# Interface.net
KiCad netlist of a schematic drawn in Altium Designer
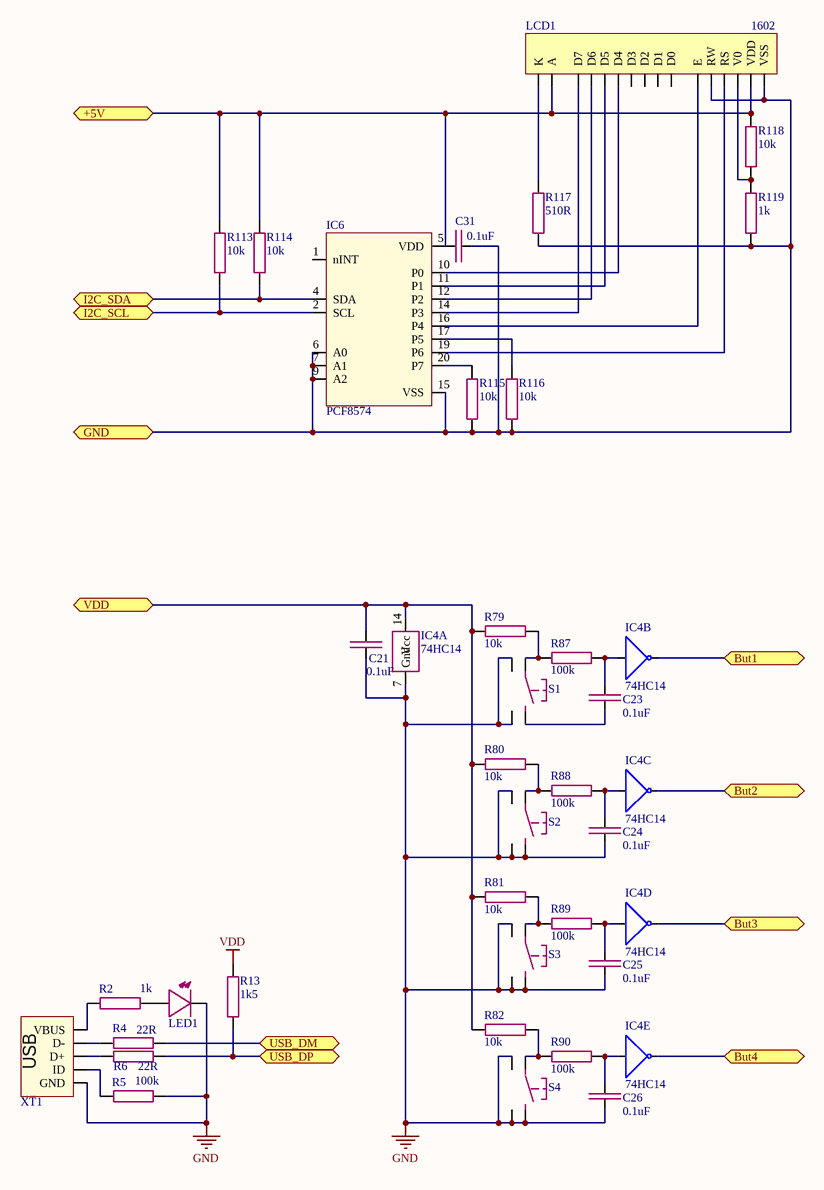
[diagram p0: Interface.SchDoc]

(export (version "E")
  (design (tool "Eeschema 10.0.6"))
  (components
    (comp (ref "C21")
      (value "0.1uF")
      (footprint "PcbLib:C0603")
      (description "CAP CER 0.1UF 50V X7R 0603")
      (fields (field (name "MANUFACTURER PART NUMBER") "GMK316F475ZG-T"))
      (libsource (lib "RCU") (part "GMK316F475ZG-T"))
    )
    (comp (ref "C23")
      (value "0.1uF")
      (footprint "PcbLib:C0603")
      (description "CAP CER 0.1UF 50V X7R 0603")
      (fields (field (name "MANUFACTURER PART NUMBER") "GMK316F475ZG-T"))
      (libsource (lib "RCU") (part "GMK316F475ZG-T"))
    )
    (comp (ref "C24")
      (value "0.1uF")
      (footprint "PcbLib:C0603")
      (description "CAP CER 0.1UF 50V X7R 0603")
      (fields (field (name "MANUFACTURER PART NUMBER") "GMK316F475ZG-T"))
      (libsource (lib "RCU") (part "GMK316F475ZG-T"))
    )
    (comp (ref "C25")
      (value "0.1uF")
      (footprint "PcbLib:C0603")
      (description "CAP CER 0.1UF 50V X7R 0603")
      (fields (field (name "MANUFACTURER PART NUMBER") "GMK316F475ZG-T"))
      (libsource (lib "RCU") (part "GMK316F475ZG-T"))
    )
    (comp (ref "C26")
      (value "0.1uF")
      (footprint "PcbLib:C0603")
      (description "CAP CER 0.1UF 50V X7R 0603")
      (fields (field (name "MANUFACTURER PART NUMBER") "GMK316F475ZG-T"))
      (libsource (lib "RCU") (part "GMK316F475ZG-T"))
    )
    (comp (ref "C31")
      (value "0.1uF")
      (footprint "PcbLib:C0603")
      (description "CAP CER 0.1UF 50V X7R 0603")
      (fields (field (name "MANUFACTURER PART NUMBER") "GMK316F475ZG-T"))
      (libsource (lib "RCU") (part "GMK316F475ZG-T"))
    )
    (comp (ref "IC4")
      (value "74HC14")
      (footprint "PcbLib:SSOP14")
      (description "IC INVERTER HEX SCHMITT 14SOIC")
      (fields (field (name "MANUFACTURER PART NUMBER") "MC74HC14ADR2G"))
      (libsource (lib "RCU") (part "MC74HC14ADR2G"))
    )
    (comp (ref "IC6")
      (value "PCF8574")
      (footprint "PcbLib:SSOP-20N")
      (description "IC I/O EXPANDER I2C 8B 20TSSOP")
      (fields (field (name "MANUFACTURER PART NUMBER") "PCF8574APWR"))
      (libsource (lib "RCU") (part "PCF8574APWR"))
    )
    (comp (ref "LCD1")
      (value "1602")
      (footprint "PcbLib:Display1602")
      (description "DISP 1602 THT")
      (libsource (lib "RCU") (part "Display1602"))
    )
    (comp (ref "LED1")
      (value "Green LED")
      (footprint "PcbLib:LED0805")
      (description "LED GREEN DIFFUSED 0805 SMD")
      (fields (field (name "MANUFACTURER PART NUMBER") "LG R971-KN-1"))
      (libsource (lib "RCU") (part "LG R971-KN-1"))
    )
    (comp (ref "R2")
      (value "1k")
      (footprint "PcbLib:R0603")
      (description "RES SMD 1K OHM 5% 1/10W 0603")
      (fields (field (name "MANUFACTURER PART NUMBER") "ERJ-3GEYJ102V"))
      (libsource (lib "RCU") (part "ERJ-3GEYJ102V"))
    )
    (comp (ref "R4")
      (value "22R")
      (footprint "PcbLib:R0603")
      (description "RES SMD 22 OHM 1% 1/10W 0603")
      (fields (field (name "MANUFACTURER PART NUMBER") "CRCW060322R0FKEA"))
      (libsource (lib "RCU") (part "CRCW060322R0FKEA"))
    )
    (comp (ref "R5")
      (value "100k")
      (footprint "PcbLib:R0603")
      (description "RES SMD 100K OHM 5% 1/10W 0603")
      (fields (field (name "MANUFACTURER PART NUMBER") "ERJ-S03J104V"))
      (libsource (lib "RCU") (part "ERJ-S03J104V"))
    )
    (comp (ref "R6")
      (value "22R")
      (footprint "PcbLib:R0603")
      (description "RES SMD 22 OHM 1% 1/10W 0603")
      (fields (field (name "MANUFACTURER PART NUMBER") "CRCW060322R0FKEA"))
      (libsource (lib "RCU") (part "CRCW060322R0FKEA"))
    )
    (comp (ref "R13")
      (value "1k5")
      (footprint "PcbLib:R0603")
      (description "RES SMD 1K5 OHM 5% 1/10W 0603")
      (fields (field (name "MANUFACTURER PART NUMBER") "CRCW06031K50JNTABC"))
      (libsource (lib "RCU") (part "CRCW06031K50JNTABC"))
    )
    (comp (ref "R79")
      (value "10k")
      (footprint "PcbLib:R0603")
      (description "RES SMD 10K OHM 5% 1/10W 0603")
      (fields (field (name "MANUFACTURER PART NUMBER") "ERJ-S03J103V"))
      (libsource (lib "RCU") (part "ERJ-S03J103V"))
    )
    (comp (ref "R80")
      (value "10k")
      (footprint "PcbLib:R0603")
      (description "RES SMD 10K OHM 5% 1/10W 0603")
      (fields (field (name "MANUFACTURER PART NUMBER") "ERJ-S03J103V"))
      (libsource (lib "RCU") (part "ERJ-S03J103V"))
    )
    (comp (ref "R81")
      (value "10k")
      (footprint "PcbLib:R0603")
      (description "RES SMD 10K OHM 5% 1/10W 0603")
      (fields (field (name "MANUFACTURER PART NUMBER") "ERJ-S03J103V"))
      (libsource (lib "RCU") (part "ERJ-S03J103V"))
    )
    (comp (ref "R82")
      (value "10k")
      (footprint "PcbLib:R0603")
      (description "RES SMD 10K OHM 5% 1/10W 0603")
      (fields (field (name "MANUFACTURER PART NUMBER") "ERJ-S03J103V"))
      (libsource (lib "RCU") (part "ERJ-S03J103V"))
    )
    (comp (ref "R87")
      (value "100k")
      (footprint "PcbLib:R0603")
      (description "RES SMD 100K OHM 5% 1/10W 0603")
      (fields (field (name "MANUFACTURER PART NUMBER") "ERJ-S03J104V"))
      (libsource (lib "RCU") (part "ERJ-S03J104V"))
    )
    (comp (ref "R88")
      (value "100k")
      (footprint "PcbLib:R0603")
      (description "RES SMD 100K OHM 5% 1/10W 0603")
      (fields (field (name "MANUFACTURER PART NUMBER") "ERJ-S03J104V"))
      (libsource (lib "RCU") (part "ERJ-S03J104V"))
    )
    (comp (ref "R89")
      (value "100k")
      (footprint "PcbLib:R0603")
      (description "RES SMD 100K OHM 5% 1/10W 0603")
      (fields (field (name "MANUFACTURER PART NUMBER") "ERJ-S03J104V"))
      (libsource (lib "RCU") (part "ERJ-S03J104V"))
    )
    (comp (ref "R90")
      (value "100k")
      (footprint "PcbLib:R0603")
      (description "RES SMD 100K OHM 5% 1/10W 0603")
      (fields (field (name "MANUFACTURER PART NUMBER") "ERJ-S03J104V"))
      (libsource (lib "RCU") (part "ERJ-S03J104V"))
    )
    (comp (ref "R113")
      (value "10k")
      (footprint "PcbLib:R0603")
      (description "RES SMD 10K OHM 5% 1/10W 0603")
      (fields (field (name "MANUFACTURER PART NUMBER") "ERJ-S03J103V"))
      (libsource (lib "RCU") (part "ERJ-S03J103V"))
    )
    (comp (ref "R114")
      (value "10k")
      (footprint "PcbLib:R0603")
      (description "RES SMD 10K OHM 5% 1/10W 0603")
      (fields (field (name "MANUFACTURER PART NUMBER") "ERJ-S03J103V"))
      (libsource (lib "RCU") (part "ERJ-S03J103V"))
    )
    (comp (ref "R115")
      (value "10k")
      (footprint "PcbLib:R0603")
      (description "RES SMD 10K OHM 5% 1/10W 0603")
      (fields (field (name "MANUFACTURER PART NUMBER") "ERJ-S03J103V"))
      (libsource (lib "RCU") (part "ERJ-S03J103V"))
    )
    (comp (ref "R116")
      (value "10k")
      (footprint "PcbLib:R0603")
      (description "RES SMD 10K OHM 5% 1/10W 0603")
      (fields (field (name "MANUFACTURER PART NUMBER") "ERJ-S03J103V"))
      (libsource (lib "RCU") (part "ERJ-S03J103V"))
    )
    (comp (ref "R117")
      (value "510R")
      (footprint "PcbLib:R0603")
      (description "RES SMD 510 OHM 5% 1/10W 0603")
      (fields (field (name "MANUFACTURER PART NUMBER") "ERJ-3GEYJ511V"))
      (libsource (lib "RCU") (part "ERJ-3GEYJ511V"))
    )
    (comp (ref "R118")
      (value "10k")
      (footprint "PcbLib:R0603")
      (description "RES SMD 10K OHM 1% 1/10W 0603")
      (fields (field (name "MANUFACTURER PART NUMBER") "CRCW060310K0FKTABC"))
      (libsource (lib "RCU") (part "CRCW060310K0FKTABC"))
    )
    (comp (ref "R119")
      (value "1k")
      (footprint "PcbLib:R0603")
      (description "RES SMD 1K OHM 5% 1/10W 0603")
      (fields (field (name "MANUFACTURER PART NUMBER") "ERJ-3GEYJ102V"))
      (libsource (lib "RCU") (part "ERJ-3GEYJ102V"))
    )
    (comp (ref "S1")
      (value "1301.9503")
      (footprint "PcbLib:SW_TACT_HOR")
      (description "SWITCH TACTILE HOR SPST-NO 0.05A 12V")
      (libsource (lib "RCU") (part "1301.9503"))
    )
    (comp (ref "S2")
      (value "1301.9503")
      (footprint "PcbLib:SW_TACT_HOR")
      (description "SWITCH TACTILE HOR SPST-NO 0.05A 12V")
      (libsource (lib "RCU") (part "1301.9503"))
    )
    (comp (ref "S3")
      (value "1301.9503")
      (footprint "PcbLib:SW_TACT_HOR")
      (description "SWITCH TACTILE HOR SPST-NO 0.05A 12V")
      (libsource (lib "RCU") (part "1301.9503"))
    )
    (comp (ref "S4")
      (value "1301.9503")
      (footprint "PcbLib:SW_TACT_HOR")
      (description "SWITCH TACTILE HOR SPST-NO 0.05A 12V")
      (libsource (lib "RCU") (part "1301.9503"))
    )
    (comp (ref "XT1")
      (value "UX60-MB-5ST")
      (footprint "PcbLib:MiniUSB")
      (description "CONN RECEPT MINI USB2.0 5POS")
      (libsource (lib "RCU") (part "UX60-MB-5ST"))
    )
  )
  (nets
    (net (code "1") (name "/+5V") (class "Default")
      (node (ref "C31") (pin "2") (pinfunction "2_2") (pintype "passive"))
      (node (ref "IC6") (pin "5") (pinfunction "VDD_5") (pintype "passive"))
      (node (ref "LCD1") (pin "15") (pinfunction "A_15") (pintype "passive"))
      (node (ref "LCD1") (pin "2") (pinfunction "VDD_2") (pintype "passive"))
      (node (ref "R113") (pin "2") (pinfunction "2_2") (pintype "passive"))
      (node (ref "R114") (pin "2") (pinfunction "2_2") (pintype "passive"))
      (node (ref "R118") (pin "2") (pinfunction "2_2") (pintype "passive"))
    )
    (net (code "2") (name "/But1") (class "Default")
      (node (ref "IC4") (pin "2") (pinfunction "2_2") (pintype "passive"))
    )
    (net (code "3") (name "/But2") (class "Default")
      (node (ref "IC4") (pin "4") (pinfunction "4_4") (pintype "passive"))
    )
    (net (code "4") (name "/But3") (class "Default")
      (node (ref "IC4") (pin "6") (pinfunction "6_6") (pintype "passive"))
    )
    (net (code "5") (name "/But4") (class "Default")
      (node (ref "IC4") (pin "8") (pinfunction "8_8") (pintype "passive"))
    )
    (net (code "6") (name "/I2C_SCL") (class "Default")
      (node (ref "IC6") (pin "2") (pinfunction "SCL_2") (pintype "passive"))
      (node (ref "R113") (pin "1") (pinfunction "1_1") (pintype "passive"))
    )
    (net (code "7") (name "/I2C_SDA") (class "Default")
      (node (ref "IC6") (pin "4") (pinfunction "SDA_4") (pintype "passive"))
      (node (ref "R114") (pin "1") (pinfunction "1_1") (pintype "passive"))
    )
    (net (code "8") (name "/USB_DM") (class "Default")
      (node (ref "R4") (pin "2") (pinfunction "2_2") (pintype "passive"))
    )
    (net (code "9") (name "/USB_DP") (class "Default")
      (node (ref "R13") (pin "1") (pinfunction "1_1") (pintype "passive"))
      (node (ref "R6") (pin "2") (pinfunction "2_2") (pintype "passive"))
    )
    (net (code "10") (name "GND") (class "Default")
      (node (ref "C21") (pin "1") (pinfunction "1_1") (pintype "passive"))
      (node (ref "C24") (pin "1") (pinfunction "1_1") (pintype "passive"))
      (node (ref "C25") (pin "1") (pinfunction "1_1") (pintype "passive"))
      (node (ref "C26") (pin "1") (pinfunction "1_1") (pintype "passive"))
      (node (ref "C31") (pin "1") (pinfunction "1_1") (pintype "passive"))
      (node (ref "IC4") (pin "7") (pinfunction "Gnd_7") (pintype "passive"))
      (node (ref "IC6") (pin "15") (pinfunction "VSS_15") (pintype "passive"))
      (node (ref "IC6") (pin "6") (pinfunction "A0_6") (pintype "passive"))
      (node (ref "IC6") (pin "7") (pinfunction "A1_7") (pintype "passive"))
      (node (ref "IC6") (pin "9") (pinfunction "A2_9") (pintype "passive"))
      (node (ref "LCD1") (pin "1") (pinfunction "VSS_1") (pintype "passive"))
      (node (ref "LCD1") (pin "5") (pinfunction "RW_5") (pintype "passive"))
      (node (ref "LED1") (pin "2") (pinfunction "Cathode_2") (pintype "passive"))
      (node (ref "R115") (pin "1") (pinfunction "1_1") (pintype "passive"))
      (node (ref "R116") (pin "1") (pinfunction "1_1") (pintype "passive"))
      (node (ref "R117") (pin "2") (pinfunction "2_2") (pintype "passive"))
      (node (ref "R119") (pin "1") (pinfunction "1_1") (pintype "passive"))
      (node (ref "R5") (pin "2") (pinfunction "2_2") (pintype "passive"))
      (node (ref "S1") (pin "1") (pinfunction "1_1") (pintype "passive"))
      (node (ref "S1") (pin "3") (pinfunction "3_3") (pintype "passive"))
      (node (ref "S2") (pin "1") (pinfunction "1_1") (pintype "passive"))
      (node (ref "S2") (pin "3") (pinfunction "3_3") (pintype "passive"))
      (node (ref "S2") (pin "4") (pinfunction "4_4") (pintype "passive"))
      (node (ref "S3") (pin "1") (pinfunction "1_1") (pintype "passive"))
      (node (ref "S3") (pin "3") (pinfunction "3_3") (pintype "passive"))
      (node (ref "S3") (pin "4") (pinfunction "4_4") (pintype "passive"))
      (node (ref "S4") (pin "1") (pinfunction "1_1") (pintype "passive"))
      (node (ref "S4") (pin "3") (pinfunction "3_3") (pintype "passive"))
      (node (ref "S4") (pin "4") (pinfunction "4_4") (pintype "passive"))
      (node (ref "XT1") (pin "5") (pinfunction "GND_5") (pintype "passive"))
    )
    (net (code "11") (name "Net-(C23-Pad1)") (class "Default")
      (node (ref "C23") (pin "1") (pinfunction "1_1") (pintype "passive"))
      (node (ref "S1") (pin "4") (pinfunction "4_4") (pintype "passive"))
    )
    (net (code "12") (name "Net-(C23-Pad2)") (class "Default")
      (node (ref "C23") (pin "2") (pinfunction "2_2") (pintype "passive"))
      (node (ref "IC4") (pin "1") (pinfunction "1_1") (pintype "passive"))
      (node (ref "R87") (pin "2") (pinfunction "2_2") (pintype "passive"))
    )
    (net (code "13") (name "Net-(C24-Pad2)") (class "Default")
      (node (ref "C24") (pin "2") (pinfunction "2_2") (pintype "passive"))
      (node (ref "IC4") (pin "3") (pinfunction "3_3") (pintype "passive"))
      (node (ref "R88") (pin "2") (pinfunction "2_2") (pintype "passive"))
    )
    (net (code "14") (name "Net-(C25-Pad2)") (class "Default")
      (node (ref "C25") (pin "2") (pinfunction "2_2") (pintype "passive"))
      (node (ref "IC4") (pin "5") (pinfunction "5_5") (pintype "passive"))
      (node (ref "R89") (pin "2") (pinfunction "2_2") (pintype "passive"))
    )
    (net (code "15") (name "Net-(C26-Pad2)") (class "Default")
      (node (ref "C26") (pin "2") (pinfunction "2_2") (pintype "passive"))
      (node (ref "IC4") (pin "9") (pinfunction "9_9") (pintype "passive"))
      (node (ref "R90") (pin "2") (pinfunction "2_2") (pintype "passive"))
    )
    (net (code "16") (name "Net-(IC6-P0)") (class "Default")
      (node (ref "IC6") (pin "10") (pinfunction "P0_10") (pintype "passive"))
      (node (ref "LCD1") (pin "11") (pinfunction "D4_11") (pintype "passive"))
    )
    (net (code "17") (name "Net-(IC6-P1)") (class "Default")
      (node (ref "IC6") (pin "11") (pinfunction "P1_11") (pintype "passive"))
      (node (ref "LCD1") (pin "12") (pinfunction "D5_12") (pintype "passive"))
    )
    (net (code "18") (name "Net-(IC6-P2)") (class "Default")
      (node (ref "IC6") (pin "12") (pinfunction "P2_12") (pintype "passive"))
      (node (ref "LCD1") (pin "13") (pinfunction "D6_13") (pintype "passive"))
    )
    (net (code "19") (name "Net-(IC6-P3)") (class "Default")
      (node (ref "IC6") (pin "14") (pinfunction "P3_14") (pintype "passive"))
      (node (ref "LCD1") (pin "14") (pinfunction "D7_14") (pintype "passive"))
    )
    (net (code "20") (name "Net-(IC6-P4)") (class "Default")
      (node (ref "IC6") (pin "16") (pinfunction "P4_16") (pintype "passive"))
      (node (ref "LCD1") (pin "6") (pinfunction "E_6") (pintype "passive"))
    )
    (net (code "21") (name "Net-(IC6-P5)") (class "Default")
      (node (ref "IC6") (pin "17") (pinfunction "P5_17") (pintype "passive"))
      (node (ref "R116") (pin "2") (pinfunction "2_2") (pintype "passive"))
    )
    (net (code "22") (name "Net-(IC6-P6)") (class "Default")
      (node (ref "IC6") (pin "19") (pinfunction "P6_19") (pintype "passive"))
      (node (ref "LCD1") (pin "4") (pinfunction "RS_4") (pintype "passive"))
    )
    (net (code "23") (name "Net-(IC6-P7)") (class "Default")
      (node (ref "IC6") (pin "20") (pinfunction "P7_20") (pintype "passive"))
      (node (ref "R115") (pin "2") (pinfunction "2_2") (pintype "passive"))
    )
    (net (code "24") (name "Net-(LCD1-K)") (class "Default")
      (node (ref "LCD1") (pin "16") (pinfunction "K_16") (pintype "passive"))
      (node (ref "R117") (pin "1") (pinfunction "1_1") (pintype "passive"))
    )
    (net (code "25") (name "Net-(LCD1-V0)") (class "Default")
      (node (ref "LCD1") (pin "3") (pinfunction "V0_3") (pintype "passive"))
      (node (ref "R118") (pin "1") (pinfunction "1_1") (pintype "passive"))
      (node (ref "R119") (pin "2") (pinfunction "2_2") (pintype "passive"))
    )
    (net (code "26") (name "Net-(LED1-Anode)") (class "Default")
      (node (ref "LED1") (pin "1") (pinfunction "Anode_1") (pintype "passive"))
      (node (ref "R2") (pin "1") (pinfunction "1_1") (pintype "passive"))
    )
    (net (code "27") (name "Net-(R79-Pad1)") (class "Default")
      (node (ref "R79") (pin "1") (pinfunction "1_1") (pintype "passive"))
      (node (ref "R87") (pin "1") (pinfunction "1_1") (pintype "passive"))
      (node (ref "S1") (pin "2") (pinfunction "2_2") (pintype "passive"))
    )
    (net (code "28") (name "Net-(R80-Pad1)") (class "Default")
      (node (ref "R80") (pin "1") (pinfunction "1_1") (pintype "passive"))
      (node (ref "R88") (pin "1") (pinfunction "1_1") (pintype "passive"))
      (node (ref "S2") (pin "2") (pinfunction "2_2") (pintype "passive"))
    )
    (net (code "29") (name "Net-(R81-Pad1)") (class "Default")
      (node (ref "R81") (pin "1") (pinfunction "1_1") (pintype "passive"))
      (node (ref "R89") (pin "1") (pinfunction "1_1") (pintype "passive"))
      (node (ref "S3") (pin "2") (pinfunction "2_2") (pintype "passive"))
    )
    (net (code "30") (name "Net-(R82-Pad1)") (class "Default")
      (node (ref "R82") (pin "1") (pinfunction "1_1") (pintype "passive"))
      (node (ref "R90") (pin "1") (pinfunction "1_1") (pintype "passive"))
      (node (ref "S4") (pin "2") (pinfunction "2_2") (pintype "passive"))
    )
    (net (code "31") (name "Net-(XT1-D+)") (class "Default")
      (node (ref "R6") (pin "1") (pinfunction "1_1") (pintype "passive"))
      (node (ref "XT1") (pin "3") (pinfunction "D+_3") (pintype "passive"))
    )
    (net (code "32") (name "Net-(XT1-D-)") (class "Default")
      (node (ref "R4") (pin "1") (pinfunction "1_1") (pintype "passive"))
      (node (ref "XT1") (pin "2") (pinfunction "D-_2") (pintype "passive"))
    )
    (net (code "33") (name "Net-(XT1-ID)") (class "Default")
      (node (ref "R5") (pin "1") (pinfunction "1_1") (pintype "passive"))
      (node (ref "XT1") (pin "4") (pinfunction "ID_4") (pintype "passive"))
    )
    (net (code "34") (name "Net-(XT1-VBUS)") (class "Default")
      (node (ref "R2") (pin "2") (pinfunction "2_2") (pintype "passive"))
      (node (ref "XT1") (pin "1") (pinfunction "VBUS_1") (pintype "passive"))
    )
    (net (code "35") (name "VDD") (class "Default")
      (node (ref "C21") (pin "2") (pinfunction "2_2") (pintype "passive"))
      (node (ref "IC4") (pin "14") (pinfunction "Vcc_14") (pintype "passive"))
      (node (ref "R13") (pin "2") (pinfunction "2_2") (pintype "passive"))
      (node (ref "R79") (pin "2") (pinfunction "2_2") (pintype "passive"))
      (node (ref "R80") (pin "2") (pinfunction "2_2") (pintype "passive"))
      (node (ref "R81") (pin "2") (pinfunction "2_2") (pintype "passive"))
      (node (ref "R82") (pin "2") (pinfunction "2_2") (pintype "passive"))
    )
    (net (code "36") (name "unconnected-(IC6-nINT-Pad1)") (class "Default")
      (node (ref "IC6") (pin "1") (pinfunction "nINT_1") (pintype "passive"))
    )
    (net (code "37") (name "unconnected-(LCD1-D0-Pad7)") (class "Default")
      (node (ref "LCD1") (pin "7") (pinfunction "D0_7") (pintype "passive"))
    )
    (net (code "38") (name "unconnected-(LCD1-D1-Pad8)") (class "Default")
      (node (ref "LCD1") (pin "8") (pinfunction "D1_8") (pintype "passive"))
    )
    (net (code "39") (name "unconnected-(LCD1-D2-Pad9)") (class "Default")
      (node (ref "LCD1") (pin "9") (pinfunction "D2_9") (pintype "passive"))
    )
    (net (code "40") (name "unconnected-(LCD1-D3-Pad10)") (class "Default")
      (node (ref "LCD1") (pin "10") (pinfunction "D3_10") (pintype "passive"))
    )
  )
)
